# LED-Lampe_MCU.net
KiCad netlist of a schematic drawn in EAGLE
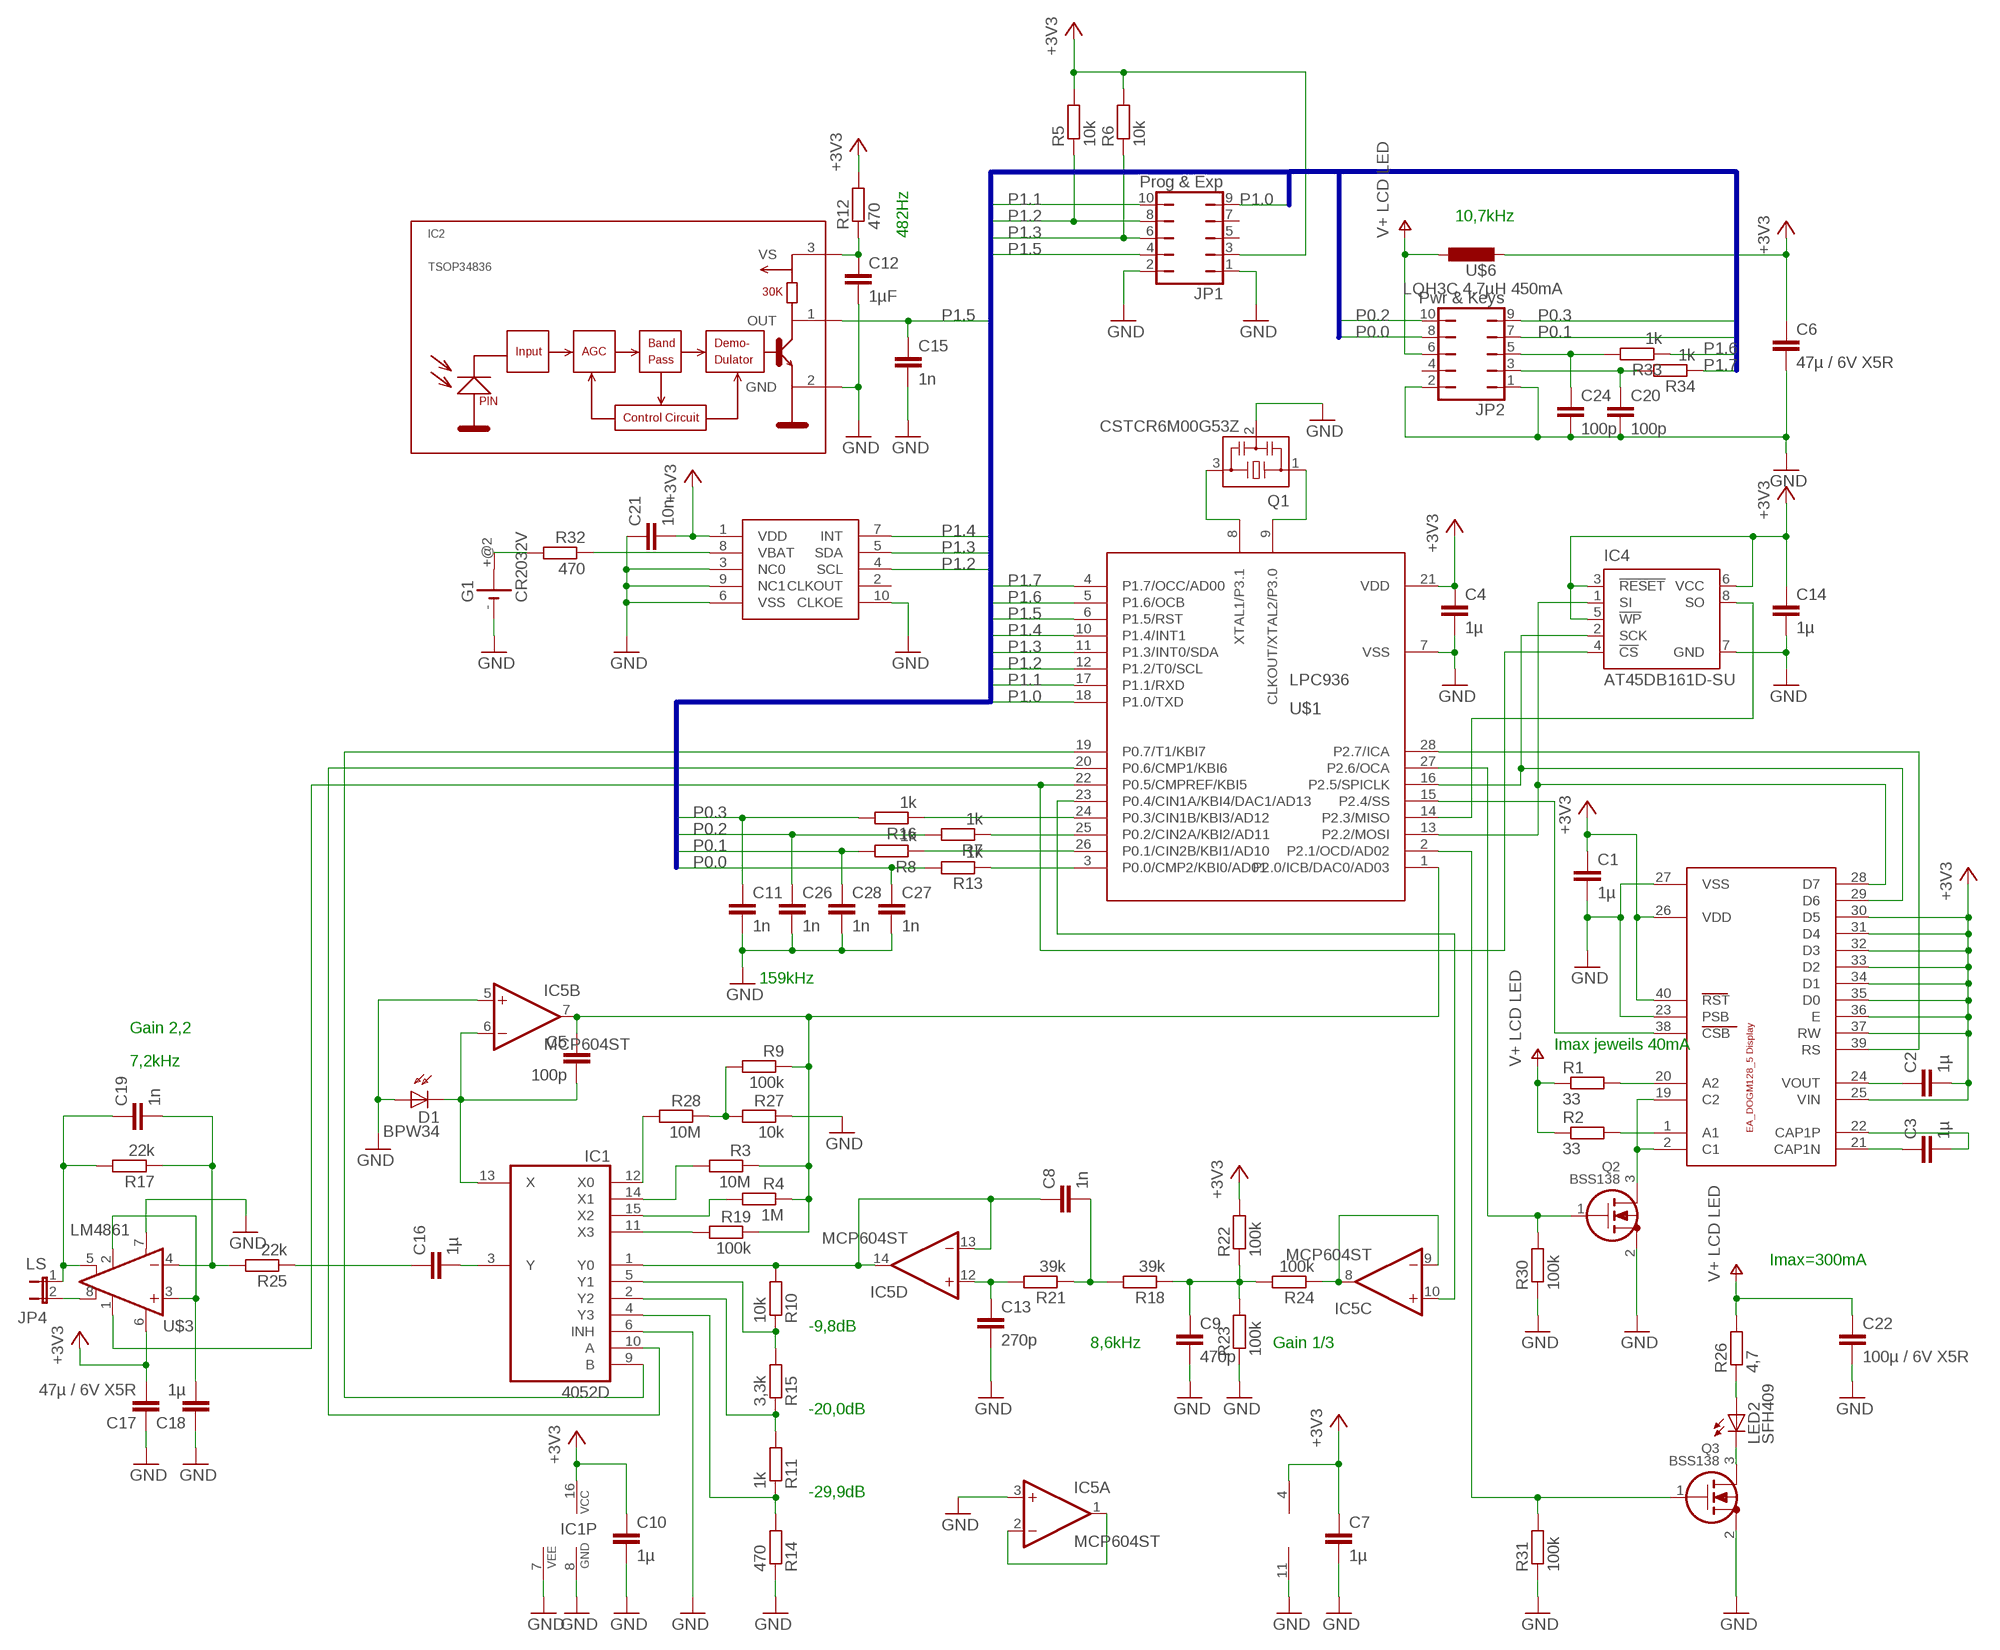
[diagram p0: schematic, sheet 1]

(export (version "E")
  (design (tool "Eeschema 10.0.6"))
  (components
    (comp (ref "C1")
      (value "1µ")
      (footprint "eagle-import:C0805")
      (libsource (lib "eagle-import") (part "C-EUC0805"))
    )
    (comp (ref "C2")
      (value "1µ")
      (footprint "eagle-import:C0805")
      (libsource (lib "eagle-import") (part "C-EUC0805"))
    )
    (comp (ref "C3")
      (value "1µ")
      (footprint "eagle-import:C0805")
      (libsource (lib "eagle-import") (part "C-EUC0805"))
    )
    (comp (ref "C4")
      (value "1µ")
      (footprint "eagle-import:C0805")
      (libsource (lib "eagle-import") (part "C-EUC0805"))
    )
    (comp (ref "C5")
      (value "100p")
      (footprint "eagle-import:C0603")
      (libsource (lib "eagle-import") (part "C-EUC0603"))
    )
    (comp (ref "C6")
      (value "47µ / 6V X5R")
      (footprint "eagle-import:C1206")
      (libsource (lib "eagle-import") (part "resistor_C-EUC1206"))
    )
    (comp (ref "C7")
      (value "1µ")
      (footprint "eagle-import:C0805")
      (libsource (lib "eagle-import") (part "C-EUC0805"))
    )
    (comp (ref "C8")
      (value "1n")
      (footprint "eagle-import:C0805")
      (libsource (lib "eagle-import") (part "C-EUC0805"))
    )
    (comp (ref "C9")
      (value "470p")
      (footprint "eagle-import:C0805")
      (libsource (lib "eagle-import") (part "C-EUC0805"))
    )
    (comp (ref "C10")
      (value "1µ")
      (footprint "eagle-import:C0805")
      (libsource (lib "eagle-import") (part "C-EUC0805"))
    )
    (comp (ref "C11")
      (value "1n")
      (footprint "eagle-import:C0603")
      (libsource (lib "eagle-import") (part "C-EUC0603"))
    )
    (comp (ref "C12")
      (value "1µF")
      (footprint "eagle-import:C0805")
      (libsource (lib "eagle-import") (part "C-EUC0805"))
    )
    (comp (ref "C13")
      (value "270p")
      (footprint "eagle-import:C0805")
      (libsource (lib "eagle-import") (part "C-EUC0805"))
    )
    (comp (ref "C14")
      (value "1µ")
      (footprint "eagle-import:C0805")
      (libsource (lib "eagle-import") (part "C-EUC0805"))
    )
    (comp (ref "C15")
      (value "1n")
      (footprint "eagle-import:C0603")
      (libsource (lib "eagle-import") (part "C-EUC0603"))
    )
    (comp (ref "C16")
      (value "1µ")
      (footprint "eagle-import:C1206")
      (libsource (lib "eagle-import") (part "C-EUC1206"))
    )
    (comp (ref "C17")
      (value "47µ / 6V X5R")
      (footprint "eagle-import:C1206")
      (libsource (lib "eagle-import") (part "C-EUC1206"))
    )
    (comp (ref "C18")
      (value "1µ")
      (footprint "eagle-import:C1206")
      (libsource (lib "eagle-import") (part "C-EUC1206"))
    )
    (comp (ref "C19")
      (value "1n")
      (footprint "eagle-import:C0805")
      (libsource (lib "eagle-import") (part "C-EUC0805"))
    )
    (comp (ref "C20")
      (value "100p")
      (footprint "eagle-import:C0603")
      (libsource (lib "eagle-import") (part "C-EUC0603"))
    )
    (comp (ref "C21")
      (value "10n")
      (footprint "eagle-import:C0805")
      (libsource (lib "eagle-import") (part "C-EUC0805"))
    )
    (comp (ref "C22")
      (value "100µ / 6V X5R")
      (footprint "eagle-import:C1206")
      (libsource (lib "eagle-import") (part "resistor_C-EUC1206"))
    )
    (comp (ref "C24")
      (value "100p")
      (footprint "eagle-import:C0603")
      (libsource (lib "eagle-import") (part "C-EUC0603"))
    )
    (comp (ref "C26")
      (value "1n")
      (footprint "eagle-import:C0603")
      (libsource (lib "eagle-import") (part "C-EUC0603"))
    )
    (comp (ref "C27")
      (value "1n")
      (footprint "eagle-import:C0603")
      (libsource (lib "eagle-import") (part "C-EUC0603"))
    )
    (comp (ref "C28")
      (value "1n")
      (footprint "eagle-import:C0603")
      (libsource (lib "eagle-import") (part "C-EUC0603"))
    )
    (comp (ref "D1")
      (value "BPW34")
      (footprint "eagle-import:BPW32")
      (libsource (lib "eagle-import") (part "BPW32"))
    )
    (comp (ref "G1")
      (value "CR2032V")
      (footprint "eagle-import:CR2032V")
      (libsource (lib "eagle-import") (part "CR2032V"))
    )
    (comp (ref "IC1")
      (value "4052D")
      (footprint "eagle-import:SO16")
      (libsource (lib "eagle-import") (part "4052D"))
    )
    (comp (ref "IC2")
      (value "TSOP34836")
      (footprint "eagle-import:TSOP348")
      (libsource (lib "eagle-import") (part "TSOP34836"))
    )
    (comp (ref "IC4")
      (value "AT45DB161D-SU")
      (footprint "eagle-import:8S2")
      (fields (field (name "MF") "ATMEL"))
      (libsource (lib "eagle-import") (part "AT45DB161D-SU"))
    )
    (comp (ref "IC5")
      (value "MCP604ST")
      (footprint "eagle-import:TSSOP14")
      (libsource (lib "eagle-import") (part "MCP604ST"))
    )
    (comp (ref "JP1")
      (value "Prog & Exp")
      (footprint "eagle-import:JP5Q")
      (libsource (lib "eagle-import") (part "JP5Q"))
    )
    (comp (ref "JP2")
      (value "Pwr & Keys")
      (footprint "eagle-import:JP5Q")
      (libsource (lib "eagle-import") (part "JP5Q"))
    )
    (comp (ref "JP4")
      (value "LS")
      (footprint "eagle-import:JP1")
      (libsource (lib "eagle-import") (part "JP1E"))
    )
    (comp (ref "LED2")
      (value "SFH409")
      (footprint "eagle-import:LED3MM")
      (libsource (lib "eagle-import") (part "LED3MM"))
    )
    (comp (ref "Q1")
      (value "CSTCR6M00G53Z")
      (footprint "eagle-import:CSTCR6M")
      (fields (field (name "MPN") "CSTCR6M00G53-R0"))
      (libsource (lib "eagle-import") (part "CSTCR6M00G53Z"))
    )
    (comp (ref "Q2")
      (value "BSS138")
      (footprint "eagle-import:SOT23")
      (libsource (lib "eagle-import") (part "BSS138"))
    )
    (comp (ref "Q3")
      (value "BSS138")
      (footprint "eagle-import:SOT23")
      (libsource (lib "eagle-import") (part "BSS138"))
    )
    (comp (ref "R1")
      (value "33")
      (footprint "eagle-import:R1206")
      (libsource (lib "eagle-import") (part "R-EU_R1206"))
    )
    (comp (ref "R2")
      (value "33")
      (footprint "eagle-import:R1206")
      (libsource (lib "eagle-import") (part "R-EU_R1206"))
    )
    (comp (ref "R3")
      (value "10M")
      (footprint "eagle-import:R0805")
      (libsource (lib "eagle-import") (part "resistor_R-EU_R0805"))
    )
    (comp (ref "R4")
      (value "1M")
      (footprint "eagle-import:R0805")
      (libsource (lib "eagle-import") (part "resistor_R-EU_R0805"))
    )
    (comp (ref "R5")
      (value "10k")
      (footprint "eagle-import:R0805")
      (libsource (lib "eagle-import") (part "R-EU_R0805"))
    )
    (comp (ref "R6")
      (value "10k")
      (footprint "eagle-import:R0805")
      (libsource (lib "eagle-import") (part "R-EU_R0805"))
    )
    (comp (ref "R7")
      (value "1k")
      (footprint "eagle-import:R0805")
      (libsource (lib "eagle-import") (part "R-EU_R0805"))
    )
    (comp (ref "R8")
      (value "1k")
      (footprint "eagle-import:R0805")
      (libsource (lib "eagle-import") (part "R-EU_R0805"))
    )
    (comp (ref "R9")
      (value "100k")
      (footprint "eagle-import:R0805")
      (libsource (lib "eagle-import") (part "resistor_R-EU_R0805"))
    )
    (comp (ref "R10")
      (value "10k")
      (footprint "eagle-import:R0805")
      (libsource (lib "eagle-import") (part "resistor_R-EU_R0805"))
    )
    (comp (ref "R11")
      (value "1k")
      (footprint "eagle-import:R0805")
      (libsource (lib "eagle-import") (part "resistor_R-EU_R0805"))
    )
    (comp (ref "R12")
      (value "470")
      (footprint "eagle-import:R0805")
      (libsource (lib "eagle-import") (part "R-EU_R0805"))
    )
    (comp (ref "R13")
      (value "1k")
      (footprint "eagle-import:R0805")
      (libsource (lib "eagle-import") (part "R-EU_R0805"))
    )
    (comp (ref "R14")
      (value "470")
      (footprint "eagle-import:R0805")
      (libsource (lib "eagle-import") (part "resistor_R-EU_R0805"))
    )
    (comp (ref "R15")
      (value "3,3k")
      (footprint "eagle-import:R0805")
      (libsource (lib "eagle-import") (part "resistor_R-EU_R0805"))
    )
    (comp (ref "R16")
      (value "1k")
      (footprint "eagle-import:R0805")
      (libsource (lib "eagle-import") (part "R-EU_R0805"))
    )
    (comp (ref "R17")
      (value "22k")
      (footprint "eagle-import:R0805")
      (libsource (lib "eagle-import") (part "R-EU_R0805"))
    )
    (comp (ref "R18")
      (value "39k")
      (footprint "eagle-import:R0805")
      (libsource (lib "eagle-import") (part "resistor_R-EU_R0805"))
    )
    (comp (ref "R19")
      (value "100k")
      (footprint "eagle-import:R0805")
      (libsource (lib "eagle-import") (part "resistor_R-EU_R0805"))
    )
    (comp (ref "R21")
      (value "39k")
      (footprint "eagle-import:R0805")
      (libsource (lib "eagle-import") (part "resistor_R-EU_R0805"))
    )
    (comp (ref "R22")
      (value "100k")
      (footprint "eagle-import:R0805")
      (libsource (lib "eagle-import") (part "resistor_R-EU_R0805"))
    )
    (comp (ref "R23")
      (value "100k")
      (footprint "eagle-import:R0805")
      (libsource (lib "eagle-import") (part "resistor_R-EU_R0805"))
    )
    (comp (ref "R24")
      (value "100k")
      (footprint "eagle-import:R0805")
      (libsource (lib "eagle-import") (part "resistor_R-EU_R0805"))
    )
    (comp (ref "R25")
      (value "22k")
      (footprint "eagle-import:R0805")
      (libsource (lib "eagle-import") (part "R-EU_R0805"))
    )
    (comp (ref "R26")
      (value "4,7")
      (footprint "eagle-import:R1206")
      (libsource (lib "eagle-import") (part "R-EU_R1206"))
    )
    (comp (ref "R27")
      (value "10k")
      (footprint "eagle-import:R0805")
      (libsource (lib "eagle-import") (part "resistor_R-EU_R0805"))
    )
    (comp (ref "R28")
      (value "10M")
      (footprint "eagle-import:R0805")
      (libsource (lib "eagle-import") (part "resistor_R-EU_R0805"))
    )
    (comp (ref "R30")
      (value "100k")
      (footprint "eagle-import:R0805")
      (libsource (lib "eagle-import") (part "R-EU_R0805"))
    )
    (comp (ref "R31")
      (value "100k")
      (footprint "eagle-import:R0805")
      (libsource (lib "eagle-import") (part "R-EU_R0805"))
    )
    (comp (ref "R32")
      (value "470")
      (footprint "eagle-import:R0805")
      (libsource (lib "eagle-import") (part "resistor_R-EU_R0805"))
    )
    (comp (ref "R33")
      (value "1k")
      (footprint "eagle-import:R0805")
      (libsource (lib "eagle-import") (part "R-EU_R0805"))
    )
    (comp (ref "R34")
      (value "1k")
      (footprint "eagle-import:R0805")
      (libsource (lib "eagle-import") (part "R-EU_R0805"))
    )
    (comp (ref "U$1")
      (value "LPC936")
      (footprint "eagle-import:TSSOP28")
      (libsource (lib "eagle-import") (part "LPC936"))
    )
    (comp (ref "U$2")
      (value "EA_DOGM162")
      (footprint "eagle-import:E_DOG-M162")
      (libsource (lib "eagle-import") (part "EA_DOGM162"))
    )
    (comp (ref "U$3")
      (value "LM4861")
      (footprint "eagle-import:SO08")
      (libsource (lib "eagle-import") (part "LM4861"))
    )
    (comp (ref "U$4")
      (value "RV3029-C2")
      (footprint "eagle-import:MC_RTC")
      (libsource (lib "eagle-import") (part "RV3029-C2"))
    )
    (comp (ref "U$6")
      (value "LQH3C 4,7µH 450mA")
      (footprint "eagle-import:L1210")
      (libsource (lib "eagle-import") (part "LQH3C"))
    )
  )
  (nets
    (net (code "1") (name "+3V3") (class "Default")
      (node (ref "C1") (pin "1") (pinfunction "1_1") (pintype "passive"))
      (node (ref "C10") (pin "1") (pinfunction "1_1") (pintype "passive"))
      (node (ref "C14") (pin "1") (pinfunction "1_1") (pintype "passive"))
      (node (ref "C17") (pin "2") (pinfunction "2_2") (pintype "passive"))
      (node (ref "C2") (pin "2") (pinfunction "2_2") (pintype "passive"))
      (node (ref "C21") (pin "2") (pinfunction "2_2") (pintype "passive"))
      (node (ref "C4") (pin "1") (pinfunction "1_1") (pintype "passive"))
      (node (ref "C6") (pin "1") (pinfunction "1_1") (pintype "passive"))
      (node (ref "C7") (pin "1") (pinfunction "1_1") (pintype "passive"))
      (node (ref "IC1") (pin "16") (pinfunction "VCC_16") (pintype "power_in"))
      (node (ref "IC4") (pin "3") (pinfunction "~{RESET}_3") (pintype "input"))
      (node (ref "IC4") (pin "5") (pinfunction "~{WP}_5") (pintype "input"))
      (node (ref "IC4") (pin "6") (pinfunction "VCC_6") (pintype "power_in"))
      (node (ref "IC5") (pin "4") (pinfunction "V+_4") (pintype "power_in"))
      (node (ref "JP1") (pin "3") (pinfunction "3_3") (pintype "passive"))
      (node (ref "R12") (pin "2") (pinfunction "2_2") (pintype "passive"))
      (node (ref "R22") (pin "2") (pinfunction "2_2") (pintype "passive"))
      (node (ref "R5") (pin "2") (pinfunction "2_2") (pintype "passive"))
      (node (ref "R6") (pin "2") (pinfunction "2_2") (pintype "passive"))
      (node (ref "U$1") (pin "21") (pinfunction "VDD_21") (pintype "bidirectional"))
      (node (ref "U$2") (pin "25") (pinfunction "VIN_25") (pintype "bidirectional"))
      (node (ref "U$2") (pin "26") (pinfunction "VDD_26") (pintype "power_in"))
      (node (ref "U$2") (pin "30") (pinfunction "D5_30") (pintype "bidirectional"))
      (node (ref "U$2") (pin "31") (pinfunction "D4_31") (pintype "bidirectional"))
      (node (ref "U$2") (pin "32") (pinfunction "D3_32") (pintype "bidirectional"))
      (node (ref "U$2") (pin "33") (pinfunction "D2_33") (pintype "bidirectional"))
      (node (ref "U$2") (pin "34") (pinfunction "D1_34") (pintype "bidirectional"))
      (node (ref "U$2") (pin "35") (pinfunction "D0_35") (pintype "bidirectional"))
      (node (ref "U$2") (pin "36") (pinfunction "E_36") (pintype "bidirectional"))
      (node (ref "U$2") (pin "37") (pinfunction "RW_37") (pintype "bidirectional"))
      (node (ref "U$2") (pin "40") (pinfunction "RST_40") (pintype "bidirectional"))
      (node (ref "U$3") (pin "6") (pinfunction "VDD_6") (pintype "power_in"))
      (node (ref "U$4") (pin "1") (pinfunction "VDD_1") (pintype "power_in"))
      (node (ref "U$6") (pin "2") (pinfunction "2_2") (pintype "passive"))
    )
    (net (code "2") (name "/P0.0") (class "Default")
      (node (ref "C27") (pin "1") (pinfunction "1_1") (pintype "passive"))
      (node (ref "JP2") (pin "8") (pinfunction "8_8") (pintype "passive"))
      (node (ref "R13") (pin "2") (pinfunction "2_2") (pintype "passive"))
    )
    (net (code "3") (name "/P0.1") (class "Default")
      (node (ref "C28") (pin "1") (pinfunction "1_1") (pintype "passive"))
      (node (ref "JP2") (pin "7") (pinfunction "7_7") (pintype "passive"))
      (node (ref "R8") (pin "2") (pinfunction "2_2") (pintype "passive"))
    )
    (net (code "4") (name "/P0.2") (class "Default")
      (node (ref "C26") (pin "1") (pinfunction "1_1") (pintype "passive"))
      (node (ref "JP2") (pin "10") (pinfunction "10_10") (pintype "passive"))
      (node (ref "R7") (pin "2") (pinfunction "2_2") (pintype "passive"))
    )
    (net (code "5") (name "/P0.3") (class "Default")
      (node (ref "C11") (pin "1") (pinfunction "1_1") (pintype "passive"))
      (node (ref "JP2") (pin "9") (pinfunction "9_9") (pintype "passive"))
      (node (ref "R16") (pin "2") (pinfunction "2_2") (pintype "passive"))
    )
    (net (code "6") (name "/P1.0") (class "Default")
      (node (ref "JP1") (pin "9") (pinfunction "9_9") (pintype "passive"))
      (node (ref "U$1") (pin "18") (pinfunction "P1.0/TXD_18") (pintype "bidirectional"))
    )
    (net (code "7") (name "/P1.1") (class "Default")
      (node (ref "JP1") (pin "10") (pinfunction "10_10") (pintype "passive"))
      (node (ref "U$1") (pin "17") (pinfunction "P1.1/RXD_17") (pintype "bidirectional"))
    )
    (net (code "8") (name "/P1.2") (class "Default")
      (node (ref "JP1") (pin "8") (pinfunction "8_8") (pintype "passive"))
      (node (ref "R5") (pin "1") (pinfunction "1_1") (pintype "passive"))
      (node (ref "U$1") (pin "12") (pinfunction "P1.2/T0/SCL_12") (pintype "bidirectional"))
      (node (ref "U$4") (pin "4") (pinfunction "SCL_4") (pintype "bidirectional"))
    )
    (net (code "9") (name "/P1.3") (class "Default")
      (node (ref "JP1") (pin "6") (pinfunction "6_6") (pintype "passive"))
      (node (ref "R6") (pin "1") (pinfunction "1_1") (pintype "passive"))
      (node (ref "U$1") (pin "11") (pinfunction "P1.3/INT0/SDA_11") (pintype "bidirectional"))
      (node (ref "U$4") (pin "5") (pinfunction "SDA_5") (pintype "bidirectional"))
    )
    (net (code "10") (name "/P1.4") (class "Default")
      (node (ref "U$1") (pin "10") (pinfunction "P1.4/INT1_10") (pintype "bidirectional"))
      (node (ref "U$4") (pin "7") (pinfunction "INT_7") (pintype "bidirectional"))
    )
    (net (code "11") (name "/P1.5") (class "Default")
      (node (ref "C15") (pin "1") (pinfunction "1_1") (pintype "passive"))
      (node (ref "IC2") (pin "1") (pinfunction "OUT_1") (pintype "output"))
      (node (ref "JP1") (pin "4") (pinfunction "4_4") (pintype "passive"))
      (node (ref "U$1") (pin "6") (pinfunction "P1.5/RST_6") (pintype "bidirectional"))
    )
    (net (code "12") (name "/P1.6") (class "Default")
      (node (ref "R33") (pin "1") (pinfunction "1_1") (pintype "passive"))
      (node (ref "U$1") (pin "5") (pinfunction "P1.6/OCB_5") (pintype "bidirectional"))
    )
    (net (code "13") (name "/P1.7") (class "Default")
      (node (ref "R34") (pin "1") (pinfunction "1_1") (pintype "passive"))
      (node (ref "U$1") (pin "4") (pinfunction "P1.7/OCC/AD00_4") (pintype "bidirectional"))
    )
    (net (code "14") (name "GND") (class "Default")
      (node (ref "C1") (pin "2") (pinfunction "2_2") (pintype "passive"))
      (node (ref "C10") (pin "2") (pinfunction "2_2") (pintype "passive"))
      (node (ref "C11") (pin "2") (pinfunction "2_2") (pintype "passive"))
      (node (ref "C12") (pin "2") (pinfunction "2_2") (pintype "passive"))
      (node (ref "C13") (pin "2") (pinfunction "2_2") (pintype "passive"))
      (node (ref "C14") (pin "2") (pinfunction "2_2") (pintype "passive"))
      (node (ref "C15") (pin "2") (pinfunction "2_2") (pintype "passive"))
      (node (ref "C17") (pin "1") (pinfunction "1_1") (pintype "passive"))
      (node (ref "C18") (pin "1") (pinfunction "1_1") (pintype "passive"))
      (node (ref "C20") (pin "2") (pinfunction "2_2") (pintype "passive"))
      (node (ref "C21") (pin "1") (pinfunction "1_1") (pintype "passive"))
      (node (ref "C22") (pin "2") (pinfunction "2_2") (pintype "passive"))
      (node (ref "C24") (pin "2") (pinfunction "2_2") (pintype "passive"))
      (node (ref "C26") (pin "2") (pinfunction "2_2") (pintype "passive"))
      (node (ref "C27") (pin "2") (pinfunction "2_2") (pintype "passive"))
      (node (ref "C28") (pin "2") (pinfunction "2_2") (pintype "passive"))
      (node (ref "C4") (pin "2") (pinfunction "2_2") (pintype "passive"))
      (node (ref "C6") (pin "2") (pinfunction "2_2") (pintype "passive"))
      (node (ref "C7") (pin "2") (pinfunction "2_2") (pintype "passive"))
      (node (ref "C9") (pin "2") (pinfunction "2_2") (pintype "passive"))
      (node (ref "D1") (pin "A") (pinfunction "A_A") (pintype "passive"))
      (node (ref "G1") (pin "-") (pinfunction "-_-") (pintype "passive"))
      (node (ref "IC1") (pin "6") (pinfunction "INH_6") (pintype "input"))
      (node (ref "IC1") (pin "7") (pinfunction "VEE_7") (pintype "power_in"))
      (node (ref "IC1") (pin "8") (pinfunction "GND_8") (pintype "power_in"))
      (node (ref "IC2") (pin "2") (pinfunction "GND_2") (pintype "power_in"))
      (node (ref "IC4") (pin "7") (pinfunction "GND_7") (pintype "power_in"))
      (node (ref "IC5") (pin "11") (pinfunction "V-_11") (pintype "power_in"))
      (node (ref "IC5") (pin "3") (pinfunction "+IN_3") (pintype "input"))
      (node (ref "IC5") (pin "5") (pinfunction "+IN_5") (pintype "input"))
      (node (ref "JP1") (pin "1") (pinfunction "1_1") (pintype "passive"))
      (node (ref "JP1") (pin "2") (pinfunction "2_2") (pintype "passive"))
      (node (ref "JP2") (pin "1") (pinfunction "1_1") (pintype "passive"))
      (node (ref "JP2") (pin "2") (pinfunction "2_2") (pintype "passive"))
      (node (ref "Q1") (pin "2") (pinfunction "2_2") (pintype "passive"))
      (node (ref "Q2") (pin "2") (pinfunction "S_2") (pintype "bidirectional"))
      (node (ref "Q3") (pin "2") (pinfunction "S_2") (pintype "bidirectional"))
      (node (ref "R14") (pin "1") (pinfunction "1_1") (pintype "passive"))
      (node (ref "R23") (pin "1") (pinfunction "1_1") (pintype "passive"))
      (node (ref "R27") (pin "1") (pinfunction "1_1") (pintype "passive"))
      (node (ref "R30") (pin "1") (pinfunction "1_1") (pintype "passive"))
      (node (ref "R31") (pin "1") (pinfunction "1_1") (pintype "passive"))
      (node (ref "U$1") (pin "7") (pinfunction "VSS_7") (pintype "bidirectional"))
      (node (ref "U$2") (pin "23") (pinfunction "PSB_23") (pintype "bidirectional"))
      (node (ref "U$2") (pin "27") (pinfunction "VSS_27") (pintype "power_in"))
      (node (ref "U$3") (pin "7") (pinfunction "GND_7") (pintype "power_in"))
      (node (ref "U$4") (pin "10") (pinfunction "CLKOE_10") (pintype "bidirectional"))
      (node (ref "U$4") (pin "3") (pinfunction "NC0_3") (pintype "bidirectional"))
      (node (ref "U$4") (pin "6") (pinfunction "VSS_6") (pintype "power_in"))
      (node (ref "U$4") (pin "9") (pinfunction "NC1_9") (pintype "bidirectional"))
    )
    (net (code "15") (name "Net-(C8-Pad2)") (class "Default")
      (node (ref "C8") (pin "2") (pinfunction "2_2") (pintype "passive"))
      (node (ref "R18") (pin "2") (pinfunction "2_2") (pintype "passive"))
      (node (ref "R21") (pin "1") (pinfunction "1_1") (pintype "passive"))
    )
    (net (code "16") (name "Net-(C9-Pad1)") (class "Default")
      (node (ref "C9") (pin "1") (pinfunction "1_1") (pintype "passive"))
      (node (ref "R18") (pin "1") (pinfunction "1_1") (pintype "passive"))
      (node (ref "R22") (pin "1") (pinfunction "1_1") (pintype "passive"))
      (node (ref "R23") (pin "2") (pinfunction "2_2") (pintype "passive"))
      (node (ref "R24") (pin "2") (pinfunction "2_2") (pintype "passive"))
    )
    (net (code "17") (name "Net-(C16-Pad1)") (class "Default")
      (node (ref "C16") (pin "1") (pinfunction "1_1") (pintype "passive"))
      (node (ref "R25") (pin "1") (pinfunction "1_1") (pintype "passive"))
    )
    (net (code "18") (name "Net-(C20-Pad1)") (class "Default")
      (node (ref "C20") (pin "1") (pinfunction "1_1") (pintype "passive"))
      (node (ref "JP2") (pin "3") (pinfunction "3_3") (pintype "passive"))
      (node (ref "R34") (pin "2") (pinfunction "2_2") (pintype "passive"))
    )
    (net (code "19") (name "Net-(C24-Pad1)") (class "Default")
      (node (ref "C24") (pin "1") (pinfunction "1_1") (pintype "passive"))
      (node (ref "JP2") (pin "5") (pinfunction "5_5") (pintype "passive"))
      (node (ref "R33") (pin "2") (pinfunction "2_2") (pintype "passive"))
    )
    (net (code "20") (name "Net-(D1-C)") (class "Default")
      (node (ref "C5") (pin "2") (pinfunction "2_2") (pintype "passive"))
      (node (ref "D1") (pin "K") (pinfunction "C_K") (pintype "passive"))
      (node (ref "IC1") (pin "13") (pinfunction "X_13") (pintype "bidirectional"))
      (node (ref "IC5") (pin "6") (pinfunction "-IN_6") (pintype "input"))
    )
    (net (code "21") (name "Net-(G1-+-Pad+@2)") (class "Default")
      (node (ref "G1") (pin "+@2") (pinfunction "+_+@2") (pintype "passive"))
      (node (ref "R32") (pin "2") (pinfunction "2_2") (pintype "passive"))
    )
    (net (code "22") (name "Net-(IC1A-A)") (class "Default")
      (node (ref "IC1") (pin "10") (pinfunction "A_10") (pintype "input"))
      (node (ref "U$1") (pin "20") (pinfunction "P0.6/CMP1/KBI6_20") (pintype "bidirectional"))
    )
    (net (code "23") (name "Net-(IC1A-B)") (class "Default")
      (node (ref "IC1") (pin "9") (pinfunction "B_9") (pintype "input"))
      (node (ref "U$1") (pin "19") (pinfunction "P0.7/T1/KBI7_19") (pintype "bidirectional"))
    )
    (net (code "24") (name "Net-(IC1A-X0)") (class "Default")
      (node (ref "IC1") (pin "12") (pinfunction "X0_12") (pintype "bidirectional"))
      (node (ref "R28") (pin "2") (pinfunction "2_2") (pintype "passive"))
    )
    (net (code "25") (name "Net-(IC1A-X1)") (class "Default")
      (node (ref "IC1") (pin "14") (pinfunction "X1_14") (pintype "bidirectional"))
      (node (ref "R3") (pin "2") (pinfunction "2_2") (pintype "passive"))
    )
    (net (code "26") (name "Net-(IC1A-X2)") (class "Default")
      (node (ref "IC1") (pin "15") (pinfunction "X2_15") (pintype "bidirectional"))
      (node (ref "R4") (pin "2") (pinfunction "2_2") (pintype "passive"))
    )
    (net (code "27") (name "Net-(IC1A-X3)") (class "Default")
      (node (ref "IC1") (pin "11") (pinfunction "X3_11") (pintype "bidirectional"))
      (node (ref "R19") (pin "2") (pinfunction "2_2") (pintype "passive"))
    )
    (net (code "28") (name "Net-(IC1A-Y)") (class "Default")
      (node (ref "C16") (pin "2") (pinfunction "2_2") (pintype "passive"))
      (node (ref "IC1") (pin "3") (pinfunction "Y_3") (pintype "bidirectional"))
    )
    (net (code "29") (name "Net-(IC1A-Y0)") (class "Default")
      (node (ref "C8") (pin "1") (pinfunction "1_1") (pintype "passive"))
      (node (ref "IC1") (pin "1") (pinfunction "Y0_1") (pintype "bidirectional"))
      (node (ref "IC5") (pin "13") (pinfunction "-IN_13") (pintype "input"))
      (node (ref "IC5") (pin "14") (pinfunction "OUT_14") (pintype "output"))
      (node (ref "R10") (pin "2") (pinfunction "2_2") (pintype "passive"))
    )
    (net (code "30") (name "Net-(IC1A-Y1)") (class "Default")
      (node (ref "IC1") (pin "5") (pinfunction "Y1_5") (pintype "bidirectional"))
      (node (ref "R10") (pin "1") (pinfunction "1_1") (pintype "passive"))
      (node (ref "R15") (pin "2") (pinfunction "2_2") (pintype "passive"))
    )
    (net (code "31") (name "Net-(IC1A-Y2)") (class "Default")
      (node (ref "IC1") (pin "2") (pinfunction "Y2_2") (pintype "bidirectional"))
      (node (ref "R11") (pin "2") (pinfunction "2_2") (pintype "passive"))
      (node (ref "R15") (pin "1") (pinfunction "1_1") (pintype "passive"))
    )
    (net (code "32") (name "Net-(IC1A-Y3)") (class "Default")
      (node (ref "IC1") (pin "4") (pinfunction "Y3_4") (pintype "bidirectional"))
      (node (ref "R11") (pin "1") (pinfunction "1_1") (pintype "passive"))
      (node (ref "R14") (pin "2") (pinfunction "2_2") (pintype "passive"))
    )
    (net (code "33") (name "Net-(IC2-VS)") (class "Default")
      (node (ref "C12") (pin "1") (pinfunction "1_1") (pintype "passive"))
      (node (ref "IC2") (pin "3") (pinfunction "VS_3") (pintype "power_in"))
      (node (ref "R12") (pin "1") (pinfunction "1_1") (pintype "passive"))
    )
    (net (code "34") (name "Net-(IC4-SCK)") (class "Default")
      (node (ref "IC4") (pin "2") (pinfunction "SCK_2") (pintype "input"))
      (node (ref "U$1") (pin "16") (pinfunction "P2.5/SPICLK_16") (pintype "bidirectional"))
      (node (ref "U$2") (pin "29") (pinfunction "D6_29") (pintype "bidirectional"))
    )
    (net (code "35") (name "Net-(IC4-SI)") (class "Default")
      (node (ref "IC4") (pin "1") (pinfunction "SI_1") (pintype "input"))
      (node (ref "U$1") (pin "13") (pinfunction "P2.2/MOSI_13") (pintype "bidirectional"))
      (node (ref "U$2") (pin "28") (pinfunction "D7_28") (pintype "bidirectional"))
    )
    (net (code "36") (name "Net-(IC4-SO)") (class "Default")
      (node (ref "IC4") (pin "8") (pinfunction "SO_8") (pintype "output"))
      (node (ref "U$1") (pin "14") (pinfunction "P2.3/MISO_14") (pintype "bidirectional"))
    )
    (net (code "37") (name "Net-(IC4-~{CS})") (class "Default")
      (node (ref "IC4") (pin "4") (pinfunction "~{CS}_4") (pintype "input"))
      (node (ref "U$1") (pin "22") (pinfunction "P0.5/CMPREF/KBI5_22") (pintype "bidirectional"))
      (node (ref "U$3") (pin "1") (pinfunction "SHUTDOWN_1") (pintype "passive"))
    )
    (net (code "38") (name "Net-(IC5A--IN)") (class "Default")
      (node (ref "IC5") (pin "1") (pinfunction "OUT_1") (pintype "output"))
      (node (ref "IC5") (pin "2") (pinfunction "-IN_2") (pintype "input"))
    )
    (net (code "39") (name "Net-(IC5B-OUT)") (class "Default")
      (node (ref "C5") (pin "1") (pinfunction "1_1") (pintype "passive"))
      (node (ref "IC5") (pin "7") (pinfunction "OUT_7") (pintype "output"))
      (node (ref "R19") (pin "1") (pinfunction "1_1") (pintype "passive"))
      (node (ref "R3") (pin "1") (pinfunction "1_1") (pintype "passive"))
      (node (ref "R4") (pin "1") (pinfunction "1_1") (pintype "passive"))
      (node (ref "R9") (pin "1") (pinfunction "1_1") (pintype "passive"))
      (node (ref "U$1") (pin "1") (pinfunction "P2.0/ICB/DAC0/AD03_1") (pintype "bidirectional"))
    )
    (net (code "40") (name "Net-(IC5C-+IN)") (class "Default")
      (node (ref "IC5") (pin "10") (pinfunction "+IN_10") (pintype "input"))
      (node (ref "U$1") (pin "23") (pinfunction "P0.4/CIN1A/KBI4/DAC1/AD13_23") (pintype "bidirectional"))
    )
    (net (code "41") (name "Net-(IC5C--IN)") (class "Default")
      (node (ref "IC5") (pin "8") (pinfunction "OUT_8") (pintype "output"))
      (node (ref "IC5") (pin "9") (pinfunction "-IN_9") (pintype "input"))
      (node (ref "R24") (pin "1") (pinfunction "1_1") (pintype "passive"))
    )
    (net (code "42") (name "Net-(IC5D-+IN)") (class "Default")
      (node (ref "C13") (pin "1") (pinfunction "1_1") (pintype "passive"))
      (node (ref "IC5") (pin "12") (pinfunction "+IN_12") (pintype "input"))
      (node (ref "R21") (pin "2") (pinfunction "2_2") (pintype "passive"))
    )
    (net (code "43") (name "Net-(LED2-C)") (class "Default")
      (node (ref "LED2") (pin "K") (pinfunction "C_K") (pintype "passive"))
      (node (ref "Q3") (pin "3") (pinfunction "D_3") (pintype "bidirectional"))
    )
    (net (code "44") (name "Net-(LED2-PadA)") (class "Default")
      (node (ref "LED2") (pin "A") (pinfunction "A_A") (pintype "passive"))
      (node (ref "R26") (pin "1") (pinfunction "1_1") (pintype "passive"))
    )
    (net (code "45") (name "Net-(Q2-D)") (class "Default")
      (node (ref "Q2") (pin "3") (pinfunction "D_3") (pintype "bidirectional"))
      (node (ref "U$2") (pin "19") (pinfunction "C2_19") (pintype "power_in"))
      (node (ref "U$2") (pin "2") (pinfunction "C1_2") (pintype "power_in"))
    )
    (net (code "46") (name "Net-(Q2-G)") (class "Default")
      (node (ref "Q2") (pin "1") (pinfunction "G_1") (pintype "bidirectional"))
      (node (ref "R30") (pin "2") (pinfunction "2_2") (pintype "passive"))
      (node (ref "U$1") (pin "27") (pinfunction "P2.6/OCA_27") (pintype "bidirectional"))
    )
    (net (code "47") (name "Net-(Q3-G)") (class "Default")
      (node (ref "Q3") (pin "1") (pinfunction "G_1") (pintype "bidirectional"))
      (node (ref "R31") (pin "2") (pinfunction "2_2") (pintype "passive"))
      (node (ref "U$1") (pin "2") (pinfunction "P2.1/OCD/AD02_2") (pintype "bidirectional"))
    )
    (net (code "48") (name "Net-(R27-Pad2)") (class "Default")
      (node (ref "R27") (pin "2") (pinfunction "2_2") (pintype "passive"))
      (node (ref "R28") (pin "1") (pinfunction "1_1") (pintype "passive"))
      (node (ref "R9") (pin "2") (pinfunction "2_2") (pintype "passive"))
    )
    (net (code "49") (name "Net-(U$1-CLKOUT{slash}XTAL2{slash}P3.0)") (class "Default")
      (node (ref "Q1") (pin "1") (pinfunction "1_1") (pintype "passive"))
      (node (ref "U$1") (pin "9") (pinfunction "CLKOUT/XTAL2/P3.0_9") (pintype "bidirectional"))
    )
    (net (code "50") (name "Net-(U$1-P0.0{slash}CMP2{slash}KBI0{slash}AD01)") (class "Default")
      (node (ref "R13") (pin "1") (pinfunction "1_1") (pintype "passive"))
      (node (ref "U$1") (pin "3") (pinfunction "P0.0/CMP2/KBI0/AD01_3") (pintype "bidirectional"))
    )
    (net (code "51") (name "Net-(U$1-P0.1{slash}CIN2B{slash}KBI1{slash}AD10)") (class "Default")
      (node (ref "R8") (pin "1") (pinfunction "1_1") (pintype "passive"))
      (node (ref "U$1") (pin "26") (pinfunction "P0.1/CIN2B/KBI1/AD10_26") (pintype "bidirectional"))
    )
    (net (code "52") (name "Net-(U$1-P0.2{slash}CIN2A{slash}KBI2{slash}AD11)") (class "Default")
      (node (ref "R7") (pin "1") (pinfunction "1_1") (pintype "passive"))
      (node (ref "U$1") (pin "25") (pinfunction "P0.2/CIN2A/KBI2/AD11_25") (pintype "bidirectional"))
    )
    (net (code "53") (name "Net-(U$1-P0.3{slash}CIN1B{slash}KBI3{slash}AD12)") (class "Default")
      (node (ref "R16") (pin "1") (pinfunction "1_1") (pintype "passive"))
      (node (ref "U$1") (pin "24") (pinfunction "P0.3/CIN1B/KBI3/AD12_24") (pintype "bidirectional"))
    )
    (net (code "54") (name "Net-(U$1-P2.4{slash}SS)") (class "Default")
      (node (ref "U$1") (pin "15") (pinfunction "P2.4/SS_15") (pintype "bidirectional"))
      (node (ref "U$2") (pin "38") (pinfunction "CSB_38") (pintype "bidirectional"))
    )
    (net (code "55") (name "Net-(U$1-P2.7{slash}ICA)") (class "Default")
      (node (ref "U$1") (pin "28") (pinfunction "P2.7/ICA_28") (pintype "bidirectional"))
      (node (ref "U$2") (pin "39") (pinfunction "RS_39") (pintype "bidirectional"))
    )
    (net (code "56") (name "Net-(U$1-XTAL1{slash}P3.1)") (class "Default")
      (node (ref "Q1") (pin "3") (pinfunction "3_3") (pintype "passive"))
      (node (ref "U$1") (pin "8") (pinfunction "XTAL1/P3.1_8") (pintype "bidirectional"))
    )
    (net (code "57") (name "Net-(U$2-A1)") (class "Default")
      (node (ref "R2") (pin "2") (pinfunction "2_2") (pintype "passive"))
      (node (ref "U$2") (pin "1") (pinfunction "A1_1") (pintype "power_in"))
    )
    (net (code "58") (name "Net-(U$2-A2)") (class "Default")
      (node (ref "R1") (pin "2") (pinfunction "2_2") (pintype "passive"))
      (node (ref "U$2") (pin "20") (pinfunction "A2_20") (pintype "power_in"))
    )
    (net (code "59") (name "Net-(U$2-CAP1N)") (class "Default")
      (node (ref "C3") (pin "1") (pinfunction "1_1") (pintype "passive"))
      (node (ref "U$2") (pin "21") (pinfunction "CAP1N_21") (pintype "bidirectional"))
    )
    (net (code "60") (name "Net-(U$2-CAP1P)") (class "Default")
      (node (ref "C3") (pin "2") (pinfunction "2_2") (pintype "passive"))
      (node (ref "U$2") (pin "22") (pinfunction "CAP1P_22") (pintype "bidirectional"))
    )
    (net (code "61") (name "Net-(U$2-VOUT)") (class "Default")
      (node (ref "C2") (pin "1") (pinfunction "1_1") (pintype "passive"))
      (node (ref "U$2") (pin "24") (pinfunction "VOUT_24") (pintype "bidirectional"))
    )
    (net (code "62") (name "Net-(U$3-+IN)") (class "Default")
      (node (ref "C18") (pin "2") (pinfunction "2_2") (pintype "passive"))
      (node (ref "U$3") (pin "2") (pinfunction "BYPASS_2") (pintype "passive"))
      (node (ref "U$3") (pin "3") (pinfunction "+IN_3") (pintype "input"))
    )
    (net (code "63") (name "Net-(U$3--IN)") (class "Default")
      (node (ref "C19") (pin "2") (pinfunction "2_2") (pintype "passive"))
      (node (ref "R17") (pin "1") (pinfunction "1_1") (pintype "passive"))
      (node (ref "R25") (pin "2") (pinfunction "2_2") (pintype "passive"))
      (node (ref "U$3") (pin "4") (pinfunction "-IN_4") (pintype "input"))
    )
    (net (code "64") (name "Net-(U$3-VO1)") (class "Default")
      (node (ref "C19") (pin "1") (pinfunction "1_1") (pintype "passive"))
      (node (ref "JP4") (pin "1") (pinfunction "1_1") (pintype "passive"))
      (node (ref "R17") (pin "2") (pinfunction "2_2") (pintype "passive"))
      (node (ref "U$3") (pin "5") (pinfunction "VO1_5") (pintype "output"))
    )
    (net (code "65") (name "Net-(U$3-VO2)") (class "Default")
      (node (ref "JP4") (pin "2") (pinfunction "2_2") (pintype "passive"))
      (node (ref "U$3") (pin "8") (pinfunction "VO2_8") (pintype "output"))
    )
    (net (code "66") (name "Net-(U$4-VBAT)") (class "Default")
      (node (ref "R32") (pin "1") (pinfunction "1_1") (pintype "passive"))
      (node (ref "U$4") (pin "8") (pinfunction "VBAT_8") (pintype "power_in"))
    )
    (net (code "67") (name "V+ LCD LED") (class "Default")
      (node (ref "C22") (pin "1") (pinfunction "1_1") (pintype "passive"))
      (node (ref "JP2") (pin "6") (pinfunction "6_6") (pintype "passive"))
      (node (ref "R1") (pin "1") (pinfunction "1_1") (pintype "passive"))
      (node (ref "R2") (pin "1") (pinfunction "1_1") (pintype "passive"))
      (node (ref "R26") (pin "2") (pinfunction "2_2") (pintype "passive"))
      (node (ref "U$6") (pin "1") (pinfunction "1_1") (pintype "passive"))
    )
    (net (code "68") (name "unconnected-(G1-Pad+)") (class "Default")
      (node (ref "G1") (pin "+") (pinfunction "+_+") (pintype "passive"))
    )
    (net (code "69") (name "unconnected-(JP1-Pad5)") (class "Default")
      (node (ref "JP1") (pin "5") (pinfunction "5_5") (pintype "passive"))
    )
    (net (code "70") (name "unconnected-(JP1-Pad7)") (class "Default")
      (node (ref "JP1") (pin "7") (pinfunction "7_7") (pintype "passive"))
    )
    (net (code "71") (name "unconnected-(JP2-Pad4)") (class "Default")
      (node (ref "JP2") (pin "4") (pinfunction "4_4") (pintype "passive"))
    )
    (net (code "72") (name "unconnected-(U$4-CLKOUT-Pad2)") (class "Default")
      (node (ref "U$4") (pin "2") (pinfunction "CLKOUT_2") (pintype "output"))
    )
  )
)
